# Circuit_V1.net
KiCad netlist of a schematic drawn in EAGLE
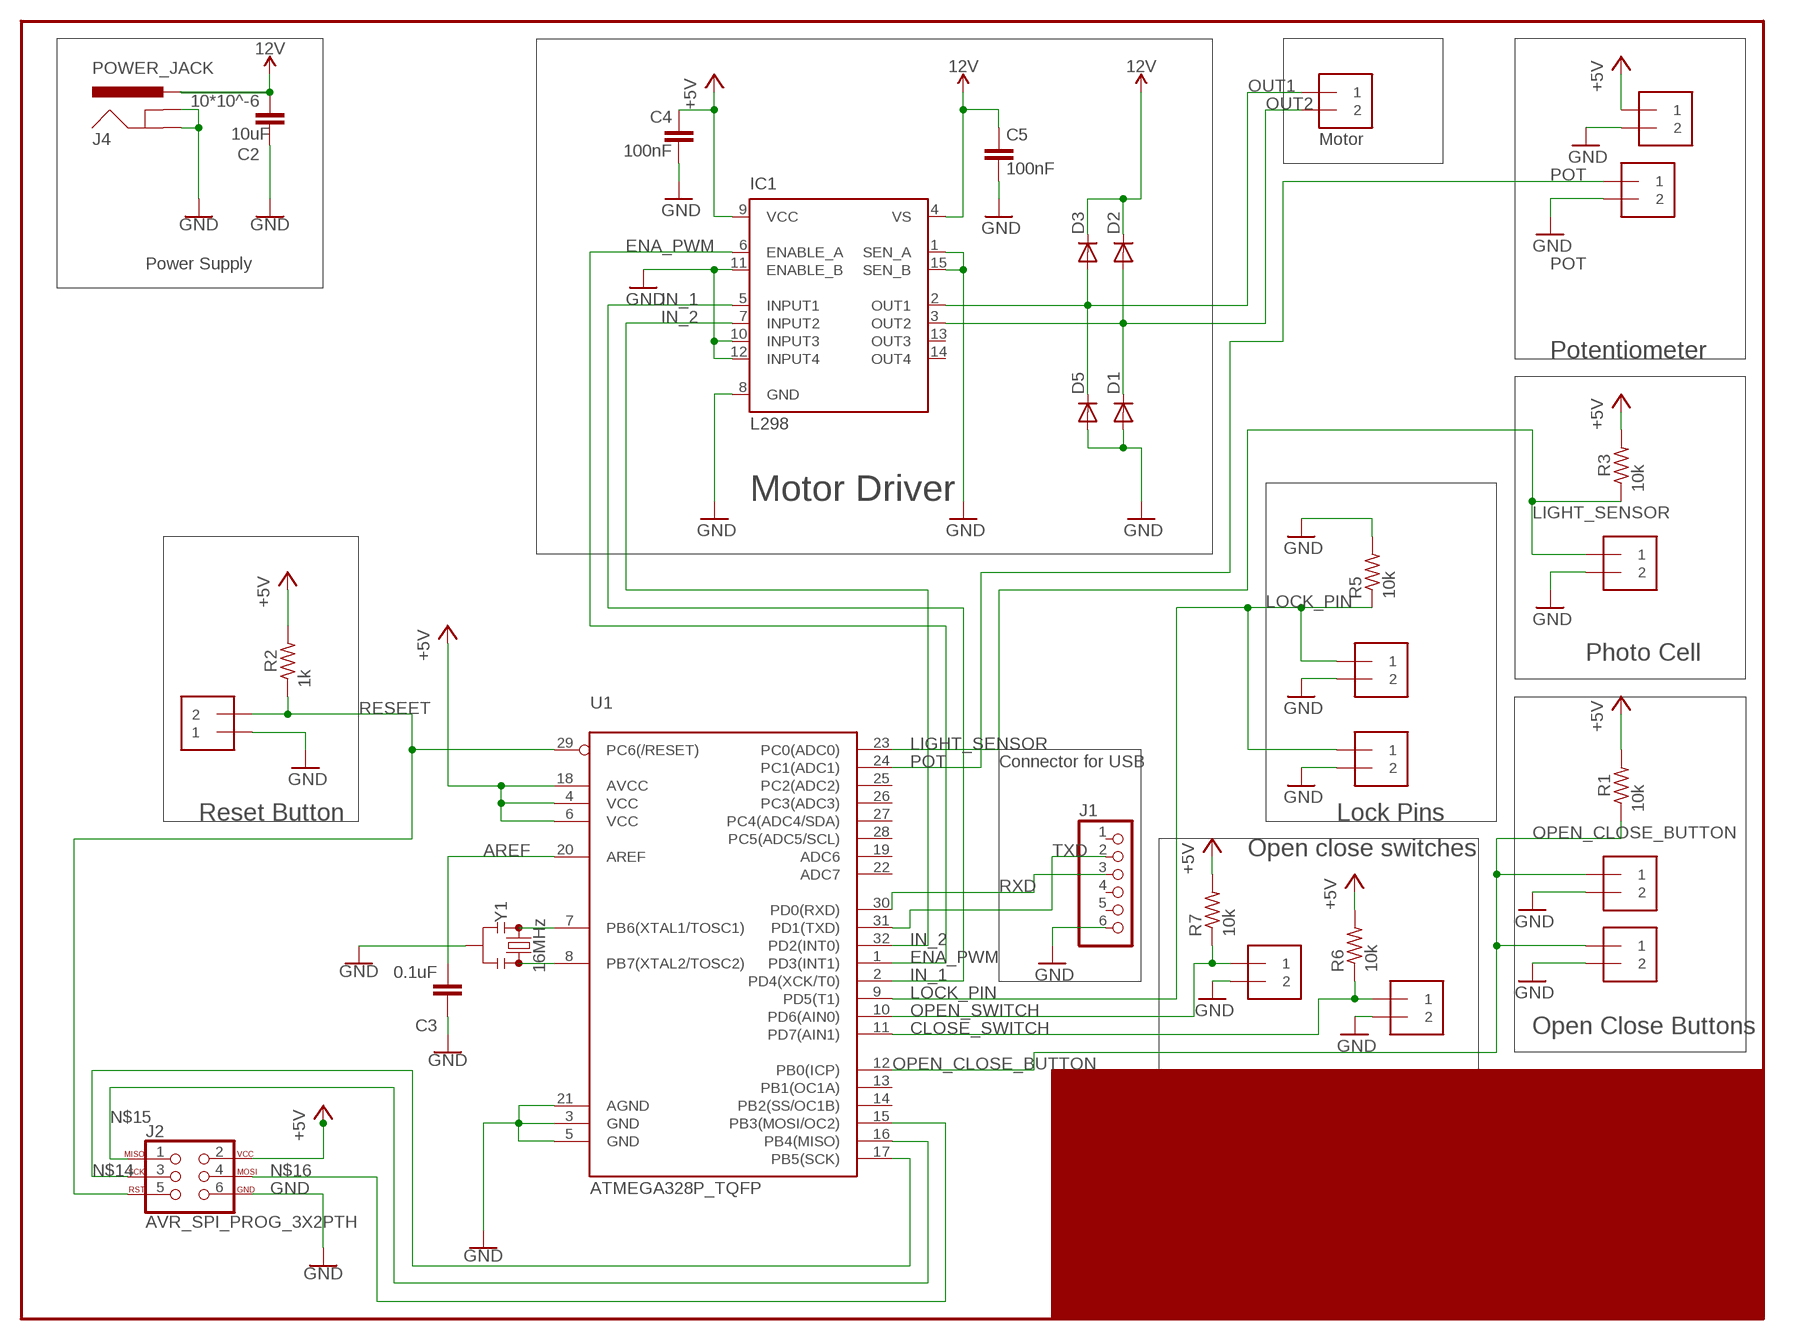
[diagram p0: schematic, sheet 1]

(export (version "E")
  (design (tool "Eeschema 10.0.6"))
  (components
    (comp (ref "C2")
      (value "10*10^-6")
      (footprint "eagle-import:C0805")
      (fields (field (name "SPICEPREFIX") "C") (field (name "SPICEPREFIX_1") "10uF"))
      (libsource (lib "eagle-import") (part "C-EUC0805"))
    )
    (comp (ref "C3")
      (value "0.1uF")
      (footprint "eagle-import:C0805")
      (libsource (lib "eagle-import") (part "C-EUC0805"))
    )
    (comp (ref "C4")
      (value "100nF")
      (footprint "eagle-import:C0805")
      (libsource (lib "eagle-import") (part "C-EUC0805"))
    )
    (comp (ref "C5")
      (value "100nF")
      (footprint "eagle-import:C0805")
      (libsource (lib "eagle-import") (part "C-EUC0805"))
    )
    (comp (ref "D1")
      (value "DIODE-DO214AA")
      (footprint "eagle-import:DO214AA")
      (libsource (lib "eagle-import") (part "DIODE-DO214AA"))
    )
    (comp (ref "D2")
      (value "DIODE-DO214AA")
      (footprint "eagle-import:DO214AA")
      (libsource (lib "eagle-import") (part "DIODE-DO214AA"))
    )
    (comp (ref "D3")
      (value "DIODE-DO214AA")
      (footprint "eagle-import:DO214AA")
      (libsource (lib "eagle-import") (part "DIODE-DO214AA"))
    )
    (comp (ref "D5")
      (value "DIODE-DO214AA")
      (footprint "eagle-import:DO214AA")
      (libsource (lib "eagle-import") (part "DIODE-DO214AA"))
    )
    (comp (ref "FRAME1")
      (value "FRAME-LETTER")
      (footprint "eagle-import:CREATIVE_COMMONS")
      (libsource (lib "eagle-import") (part "FRAME-LETTER"))
    )
    (comp (ref "IC1")
      (value "L298")
      (footprint "eagle-import:MULTIWATT-15")
      (fields (field (name "MPN") "L298N"))
      (libsource (lib "eagle-import") (part "L298"))
    )
    (comp (ref "INSIDE_BUTTON")
      (value "1X2-3.5MM")
      (footprint "eagle-import:1X2-3.5MM")
      (libsource (lib "eagle-import") (part "1X2-3.5MM"))
    )
    (comp (ref "INSIDE_OPEN_BUTTON")
      (value "1X2-3.5MM")
      (footprint "eagle-import:1X2-3.5MM")
      (libsource (lib "eagle-import") (part "1X2-3.5MM"))
    )
    (comp (ref "J1")
      (value "PINHD-1X6")
      (footprint "eagle-import:1X06")
      (libsource (lib "eagle-import") (part "PINHD-1X6"))
    )
    (comp (ref "J2")
      (value "AVR_SPI_PROG_3X2PTH")
      (footprint "eagle-import:2X3")
      (libsource (lib "eagle-import") (part "AVR_SPI_PROG_3X2PTH"))
    )
    (comp (ref "J4")
      (value "POWER_JACK")
      (footprint "eagle-import:POWER_JACK_PTH")
      (libsource (lib "eagle-import") (part "POWER_JACK"))
    )
    (comp (ref "LIGHT_SENSOR")
      (value "1X2-3.5MM")
      (footprint "eagle-import:1X2-3.5MM")
      (libsource (lib "eagle-import") (part "1X2-3.5MM"))
    )
    (comp (ref "LOCK_PIN1")
      (value "1X2-3.5MM")
      (footprint "eagle-import:1X2-3.5MM")
      (libsource (lib "eagle-import") (part "1X2-3.5MM"))
    )
    (comp (ref "LOCK_PIN2")
      (value "1X2-3.5MM")
      (footprint "eagle-import:1X2-3.5MM")
      (libsource (lib "eagle-import") (part "1X2-3.5MM"))
    )
    (comp (ref "MOTOR")
      (value "1X2-3.5MM")
      (footprint "eagle-import:1X2-3.5MM")
      (libsource (lib "eagle-import") (part "1X2-3.5MM"))
    )
    (comp (ref "OUTSIDE_BUTTON")
      (value "1X2-3.5MM")
      (footprint "eagle-import:1X2-3.5MM")
      (libsource (lib "eagle-import") (part "1X2-3.5MM"))
    )
    (comp (ref "OUTSIDE_OPEN_BUTTON")
      (value "1X2-3.5MM")
      (footprint "eagle-import:1X2-3.5MM")
      (libsource (lib "eagle-import") (part "1X2-3.5MM"))
    )
    (comp (ref "POT")
      (value "1X2-3.5MM")
      (footprint "eagle-import:1X2-3.5MM")
      (libsource (lib "eagle-import") (part "1X2-3.5MM"))
    )
    (comp (ref "POTPOWER")
      (value "1X2-3.5MM")
      (footprint "eagle-import:1X2-3.5MM")
      (libsource (lib "eagle-import") (part "1X2-3.5MM"))
    )
    (comp (ref "R1")
      (value "10k")
      (footprint "eagle-import:M0805")
      (libsource (lib "eagle-import") (part "R-US_M0805"))
    )
    (comp (ref "R2")
      (value "1k")
      (footprint "eagle-import:M0805")
      (libsource (lib "eagle-import") (part "R-US_M0805"))
    )
    (comp (ref "R3")
      (value "10k")
      (footprint "eagle-import:M0805")
      (libsource (lib "eagle-import") (part "R-US_M0805"))
    )
    (comp (ref "R5")
      (value "10k")
      (footprint "eagle-import:M0805")
      (libsource (lib "eagle-import") (part "R-US_M0805"))
    )
    (comp (ref "R6")
      (value "10k")
      (footprint "eagle-import:M0805")
      (libsource (lib "eagle-import") (part "R-US_M0805"))
    )
    (comp (ref "R7")
      (value "10k")
      (footprint "eagle-import:M0805")
      (libsource (lib "eagle-import") (part "R-US_M0805"))
    )
    (comp (ref "RESETBUTTON")
      (value "1X2-3.5MM")
      (footprint "eagle-import:1X2-3.5MM")
      (libsource (lib "eagle-import") (part "1X2-3.5MM"))
    )
    (comp (ref "U1")
      (value "ATMEGA328P_TQFP")
      (footprint "eagle-import:TQFP32-08")
      (libsource (lib "eagle-import") (part "ATMEGA328P_TQFP"))
    )
    (comp (ref "Y1")
      (value "16MHz")
      (footprint "eagle-import:RESONATOR-SMD-3.2X1.3")
      (libsource (lib "eagle-import") (part "RESONATOR-16MHZSMD_3.2X1.3"))
    )
  )
  (nets
    (net (code "1") (name "+5V") (class "Default")
      (node (ref "C4") (pin "1") (pinfunction "1_1") (pintype "passive"))
      (node (ref "IC1") (pin "9") (pinfunction "VCC_9") (pintype "power_in"))
      (node (ref "J2") (pin "2") (pinfunction "2_2") (pintype "passive"))
      (node (ref "POTPOWER") (pin "1") (pinfunction "1_1") (pintype "passive"))
      (node (ref "R1") (pin "2") (pinfunction "2_2") (pintype "passive"))
      (node (ref "R2") (pin "2") (pinfunction "2_2") (pintype "passive"))
      (node (ref "R3") (pin "2") (pinfunction "2_2") (pintype "passive"))
      (node (ref "R6") (pin "2") (pinfunction "2_2") (pintype "passive"))
      (node (ref "R7") (pin "2") (pinfunction "2_2") (pintype "passive"))
      (node (ref "U1") (pin "18") (pinfunction "AVCC_18") (pintype "bidirectional"))
      (node (ref "U1") (pin "4") (pinfunction "VCC_4") (pintype "bidirectional"))
      (node (ref "U1") (pin "6") (pinfunction "VCC_6") (pintype "bidirectional"))
    )
    (net (code "2") (name "/AREF") (class "Default")
      (node (ref "C3") (pin "2") (pinfunction "2_2") (pintype "passive"))
      (node (ref "U1") (pin "20") (pinfunction "AREF_20") (pintype "bidirectional"))
    )
    (net (code "3") (name "/CLOSE_SWITCH") (class "Default")
      (node (ref "INSIDE_OPEN_BUTTON") (pin "1") (pinfunction "1_1") (pintype "passive"))
      (node (ref "R6") (pin "1") (pinfunction "1_1") (pintype "passive"))
      (node (ref "U1") (pin "11") (pinfunction "PD7(AIN1)_11") (pintype "bidirectional"))
    )
    (net (code "4") (name "/ENA_PWM") (class "Default")
      (node (ref "IC1") (pin "6") (pinfunction "ENABLE_A_6") (pintype "input"))
      (node (ref "U1") (pin "1") (pinfunction "PD3(INT1)_1") (pintype "bidirectional"))
    )
    (net (code "5") (name "/IN_1") (class "Default")
      (node (ref "IC1") (pin "5") (pinfunction "INPUT1_5") (pintype "input"))
      (node (ref "U1") (pin "2") (pinfunction "PD4(XCK/T0)_2") (pintype "bidirectional"))
    )
    (net (code "6") (name "/IN_2") (class "Default")
      (node (ref "IC1") (pin "7") (pinfunction "INPUT2_7") (pintype "input"))
      (node (ref "U1") (pin "32") (pinfunction "PD2(INT0)_32") (pintype "bidirectional"))
    )
    (net (code "7") (name "/LIGHT_SENSOR") (class "Default")
      (node (ref "LIGHT_SENSOR") (pin "1") (pinfunction "1_1") (pintype "passive"))
      (node (ref "R3") (pin "1") (pinfunction "1_1") (pintype "passive"))
      (node (ref "U1") (pin "23") (pinfunction "PC0(ADC0)_23") (pintype "bidirectional"))
    )
    (net (code "8") (name "/LOCK_PIN") (class "Default")
      (node (ref "LOCK_PIN1") (pin "1") (pinfunction "1_1") (pintype "passive"))
      (node (ref "LOCK_PIN2") (pin "1") (pinfunction "1_1") (pintype "passive"))
      (node (ref "R5") (pin "1") (pinfunction "1_1") (pintype "passive"))
      (node (ref "U1") (pin "9") (pinfunction "PD5(T1)_9") (pintype "bidirectional"))
    )
    (net (code "9") (name "/N$14") (class "Default")
      (node (ref "J2") (pin "3") (pinfunction "3_3") (pintype "passive"))
      (node (ref "U1") (pin "17") (pinfunction "PB5(SCK)_17") (pintype "bidirectional"))
    )
    (net (code "10") (name "/N$15") (class "Default")
      (node (ref "J2") (pin "1") (pinfunction "1_1") (pintype "passive"))
      (node (ref "U1") (pin "16") (pinfunction "PB4(MISO)_16") (pintype "bidirectional"))
    )
    (net (code "11") (name "/N$16") (class "Default")
      (node (ref "J2") (pin "4") (pinfunction "4_4") (pintype "passive"))
      (node (ref "U1") (pin "15") (pinfunction "PB3(MOSI/OC2)_15") (pintype "bidirectional"))
    )
    (net (code "12") (name "/OPEN_CLOSE_BUTTON") (class "Default")
      (node (ref "INSIDE_BUTTON") (pin "1") (pinfunction "1_1") (pintype "passive"))
      (node (ref "OUTSIDE_BUTTON") (pin "1") (pinfunction "1_1") (pintype "passive"))
      (node (ref "R1") (pin "1") (pinfunction "1_1") (pintype "passive"))
      (node (ref "U1") (pin "12") (pinfunction "PB0(ICP)_12") (pintype "bidirectional"))
    )
    (net (code "13") (name "/OPEN_SWITCH") (class "Default")
      (node (ref "OUTSIDE_OPEN_BUTTON") (pin "1") (pinfunction "1_1") (pintype "passive"))
      (node (ref "R7") (pin "1") (pinfunction "1_1") (pintype "passive"))
      (node (ref "U1") (pin "10") (pinfunction "PD6(AIN0)_10") (pintype "bidirectional"))
    )
    (net (code "14") (name "/OUT1") (class "Default")
      (node (ref "D3") (pin "A") (pinfunction "A_A") (pintype "passive"))
      (node (ref "D5") (pin "C") (pinfunction "C_C") (pintype "passive"))
      (node (ref "IC1") (pin "2") (pinfunction "OUT1_2") (pintype "output"))
      (node (ref "MOTOR") (pin "1") (pinfunction "1_1") (pintype "passive"))
    )
    (net (code "15") (name "/OUT2") (class "Default")
      (node (ref "D1") (pin "C") (pinfunction "C_C") (pintype "passive"))
      (node (ref "D2") (pin "A") (pinfunction "A_A") (pintype "passive"))
      (node (ref "IC1") (pin "3") (pinfunction "OUT2_3") (pintype "output"))
      (node (ref "MOTOR") (pin "2") (pinfunction "2_2") (pintype "passive"))
    )
    (net (code "16") (name "/POT") (class "Default")
      (node (ref "POT") (pin "1") (pinfunction "1_1") (pintype "passive"))
      (node (ref "U1") (pin "24") (pinfunction "PC1(ADC1)_24") (pintype "bidirectional"))
    )
    (net (code "17") (name "/RESEET") (class "Default")
      (node (ref "J2") (pin "5") (pinfunction "5_5") (pintype "passive"))
      (node (ref "R2") (pin "1") (pinfunction "1_1") (pintype "passive"))
      (node (ref "RESETBUTTON") (pin "2") (pinfunction "2_2") (pintype "passive"))
      (node (ref "U1") (pin "29") (pinfunction "PC6(/RESET)_29") (pintype "bidirectional"))
    )
    (net (code "18") (name "/RXD") (class "Default")
      (node (ref "J1") (pin "3") (pinfunction "3_3") (pintype "passive"))
      (node (ref "U1") (pin "30") (pinfunction "PD0(RXD)_30") (pintype "bidirectional"))
    )
    (net (code "19") (name "/TXD") (class "Default")
      (node (ref "J1") (pin "2") (pinfunction "2_2") (pintype "passive"))
      (node (ref "U1") (pin "31") (pinfunction "PD1(TXD)_31") (pintype "bidirectional"))
    )
    (net (code "20") (name "12V") (class "Default")
      (node (ref "C2") (pin "2") (pinfunction "2_2") (pintype "passive"))
      (node (ref "C5") (pin "1") (pinfunction "1_1") (pintype "passive"))
      (node (ref "D2") (pin "C") (pinfunction "C_C") (pintype "passive"))
      (node (ref "D3") (pin "C") (pinfunction "C_C") (pintype "passive"))
      (node (ref "IC1") (pin "4") (pinfunction "VS_4") (pintype "power_in"))
      (node (ref "J4") (pin "PWR") (pinfunction "PWR_PWR") (pintype "bidirectional"))
    )
    (net (code "21") (name "GND") (class "Default")
      (node (ref "C2") (pin "1") (pinfunction "1_1") (pintype "passive"))
      (node (ref "C3") (pin "1") (pinfunction "1_1") (pintype "passive"))
      (node (ref "C4") (pin "2") (pinfunction "2_2") (pintype "passive"))
      (node (ref "C5") (pin "2") (pinfunction "2_2") (pintype "passive"))
      (node (ref "D1") (pin "A") (pinfunction "A_A") (pintype "passive"))
      (node (ref "D5") (pin "A") (pinfunction "A_A") (pintype "passive"))
      (node (ref "IC1") (pin "1") (pinfunction "SEN_A_1") (pintype "input"))
      (node (ref "IC1") (pin "10") (pinfunction "INPUT3_10") (pintype "input"))
      (node (ref "IC1") (pin "11") (pinfunction "ENABLE_B_11") (pintype "input"))
      (node (ref "IC1") (pin "12") (pinfunction "INPUT4_12") (pintype "input"))
      (node (ref "IC1") (pin "15") (pinfunction "SEN_B_15") (pintype "input"))
      (node (ref "IC1") (pin "8") (pinfunction "GND_8") (pintype "power_in"))
      (node (ref "INSIDE_BUTTON") (pin "2") (pinfunction "2_2") (pintype "passive"))
      (node (ref "INSIDE_OPEN_BUTTON") (pin "2") (pinfunction "2_2") (pintype "passive"))
      (node (ref "J1") (pin "6") (pinfunction "6_6") (pintype "passive"))
      (node (ref "J2") (pin "6") (pinfunction "6_6") (pintype "passive"))
      (node (ref "J4") (pin "GND") (pinfunction "GND_GND") (pintype "bidirectional"))
      (node (ref "J4") (pin "GNDBREAK") (pinfunction "GNDBREAK_GNDBREAK") (pintype "bidirectional"))
      (node (ref "LIGHT_SENSOR") (pin "2") (pinfunction "2_2") (pintype "passive"))
      (node (ref "LOCK_PIN1") (pin "2") (pinfunction "2_2") (pintype "passive"))
      (node (ref "LOCK_PIN2") (pin "2") (pinfunction "2_2") (pintype "passive"))
      (node (ref "OUTSIDE_BUTTON") (pin "2") (pinfunction "2_2") (pintype "passive"))
      (node (ref "OUTSIDE_OPEN_BUTTON") (pin "2") (pinfunction "2_2") (pintype "passive"))
      (node (ref "POT") (pin "2") (pinfunction "2_2") (pintype "passive"))
      (node (ref "POTPOWER") (pin "2") (pinfunction "2_2") (pintype "passive"))
      (node (ref "R5") (pin "2") (pinfunction "2_2") (pintype "passive"))
      (node (ref "RESETBUTTON") (pin "1") (pinfunction "1_1") (pintype "passive"))
      (node (ref "U1") (pin "21") (pinfunction "AGND_21") (pintype "bidirectional"))
      (node (ref "U1") (pin "3") (pinfunction "GND_3") (pintype "bidirectional"))
      (node (ref "U1") (pin "5") (pinfunction "GND_5") (pintype "bidirectional"))
      (node (ref "Y1") (pin "2") (pinfunction "2_2") (pintype "passive"))
    )
    (net (code "22") (name "Net-(U1-PB6(XTAL1{slash}TOSC1))") (class "Default")
      (node (ref "U1") (pin "7") (pinfunction "PB6(XTAL1/TOSC1)_7") (pintype "bidirectional"))
      (node (ref "Y1") (pin "1") (pinfunction "1_1") (pintype "passive"))
    )
    (net (code "23") (name "Net-(U1-PB7(XTAL2{slash}TOSC2))") (class "Default")
      (node (ref "U1") (pin "8") (pinfunction "PB7(XTAL2/TOSC2)_8") (pintype "bidirectional"))
      (node (ref "Y1") (pin "3") (pinfunction "3_3") (pintype "passive"))
    )
    (net (code "24") (name "unconnected-(IC1-OUT3-Pad13)") (class "Default")
      (node (ref "IC1") (pin "13") (pinfunction "OUT3_13") (pintype "output"))
    )
    (net (code "25") (name "unconnected-(IC1-OUT4-Pad14)") (class "Default")
      (node (ref "IC1") (pin "14") (pinfunction "OUT4_14") (pintype "output"))
    )
    (net (code "26") (name "unconnected-(J1-Pad1)") (class "Default")
      (node (ref "J1") (pin "1") (pinfunction "1_1") (pintype "passive"))
    )
    (net (code "27") (name "unconnected-(J1-Pad4)") (class "Default")
      (node (ref "J1") (pin "4") (pinfunction "4_4") (pintype "passive"))
    )
    (net (code "28") (name "unconnected-(J1-Pad5)") (class "Default")
      (node (ref "J1") (pin "5") (pinfunction "5_5") (pintype "passive"))
    )
    (net (code "29") (name "unconnected-(U1-ADC6-Pad19)") (class "Default")
      (node (ref "U1") (pin "19") (pinfunction "ADC6_19") (pintype "bidirectional"))
    )
    (net (code "30") (name "unconnected-(U1-ADC7-Pad22)") (class "Default")
      (node (ref "U1") (pin "22") (pinfunction "ADC7_22") (pintype "bidirectional"))
    )
    (net (code "31") (name "unconnected-(U1-PB1(OC1A)-Pad13)") (class "Default")
      (node (ref "U1") (pin "13") (pinfunction "PB1(OC1A)_13") (pintype "bidirectional"))
    )
    (net (code "32") (name "unconnected-(U1-PB2(SS{slash}OC1B)-Pad14)") (class "Default")
      (node (ref "U1") (pin "14") (pinfunction "PB2(SS/OC1B)_14") (pintype "bidirectional"))
    )
    (net (code "33") (name "unconnected-(U1-PC2(ADC2)-Pad25)") (class "Default")
      (node (ref "U1") (pin "25") (pinfunction "PC2(ADC2)_25") (pintype "bidirectional"))
    )
    (net (code "34") (name "unconnected-(U1-PC3(ADC3)-Pad26)") (class "Default")
      (node (ref "U1") (pin "26") (pinfunction "PC3(ADC3)_26") (pintype "bidirectional"))
    )
    (net (code "35") (name "unconnected-(U1-PC4(ADC4{slash}SDA)-Pad27)") (class "Default")
      (node (ref "U1") (pin "27") (pinfunction "PC4(ADC4/SDA)_27") (pintype "bidirectional"))
    )
    (net (code "36") (name "unconnected-(U1-PC5(ADC5{slash}SCL)-Pad28)") (class "Default")
      (node (ref "U1") (pin "28") (pinfunction "PC5(ADC5/SCL)_28") (pintype "bidirectional"))
    )
  )
)
